# Tag201_GangProgrammerColumnRev1.net
KiCad netlist of a schematic drawn in Altium Designer
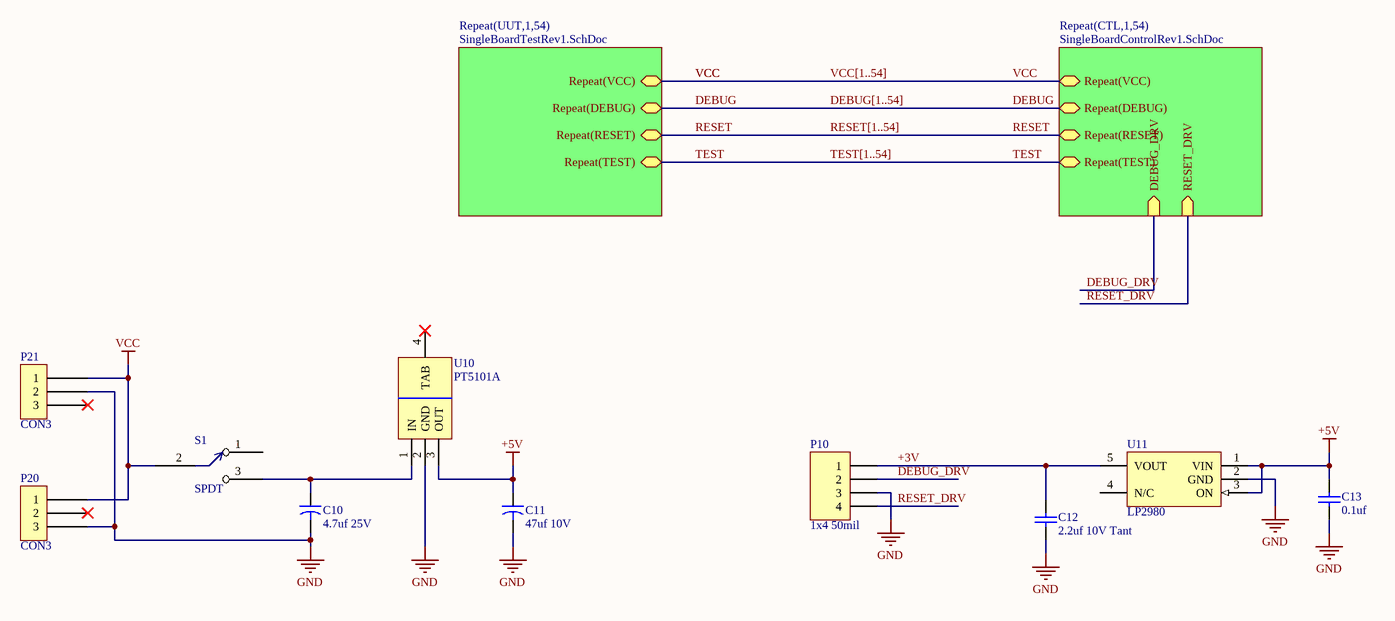
[diagram p0: Tag201_GangProgrammerColumnRev1.SchDoc]

(export (version "E")
  (design (tool "Eeschema 10.0.6"))
  (components
    (comp (ref "C10")
      (value "4.7uf 25V")
      (footprint "CAP C CASE_041412")
      (description "Capacitor")
      (fields (field (name "PARTNO") "T491A475M025AT"))
      (libsource (lib "Miscellaneous Devices") (part "Cap2"))
    )
    (comp (ref "C11")
      (value "47uf 10V")
      (footprint "CAP D CASE_030205")
      (description "Capacitor")
      (fields (field (name "PARTNO") "TAJC476K010RNJ"))
      (libsource (lib "Miscellaneous Devices") (part "Cap2"))
    )
    (comp (ref "C12")
      (value "2.2uf 10V Tant")
      (footprint "CAP A CASE_030205")
      (description "Capacitor")
      (fields (field (name "PARTNO") "F931A225MAA"))
      (libsource (lib "Miscellaneous Devices") (part "Cap"))
    )
    (comp (ref "C13")
      (value "0.1uf")
      (footprint "0603_072205")
      (description "Capacitor")
      (fields (field (name "PARTNO") "C0603C104Z3VACTU"))
      (libsource (lib "Miscellaneous Devices") (part "Cap"))
    )
    (comp (ref "P10")
      (value "1x4 50mil")
      (footprint "1X4 HEADER_50mil_071411")
      (description "Header, 4-Pin")
      (libsource (lib "Miscellaneous Connectors") (part "Header 4"))
    )
    (comp (ref "P20")
      (value "CON3")
      (footprint "POWER JACK_SMALLHOLE_022110")
      (fields (field (name "PARTNO") "PJ-102A"))
      (libsource (lib "Common") (part "CON3"))
    )
    (comp (ref "P21")
      (value "CON3")
      (footprint "Power Jack_SMT_071312")
      (fields (field (name "PARTNO") "PJ-002A-SMT"))
      (libsource (lib "Common") (part "CON3"))
    )
    (comp (ref "S1")
      (value "SPDT")
      (footprint "CnK_TseriesSPDT_Toggle_040512")
      (fields (field (name "PARTNO") "T102SHCQE"))
      (libsource (lib "Common") (part "SWITCH SPST"))
    )
    (comp (ref "U10")
      (value "PT5101A")
      (footprint "TI_PowerTrendsPT_061812")
      (libsource (lib "Common") (part "LM340T"))
    )
    (comp (ref "U11")
      (value "LP2980")
      (footprint "SOT25_030205")
      (fields (field (name "PARTNO") "LP2980AIM5-3.3/NOPB"))
      (libsource (lib "Common") (part "LP2985"))
    )
  )
  (nets
    (net (code "217") (name "+5V") (class "Default")
      (node (ref "C11") (pin "1") (pinfunction "1_1") (pintype "passive"))
      (node (ref "C13") (pin "1") (pinfunction "1_1") (pintype "passive"))
      (node (ref "U10") (pin "3") (pinfunction "OUT_3") (pintype "passive"))
      (node (ref "U11") (pin "1") (pinfunction "VIN_1") (pintype "power_in"))
      (node (ref "U11") (pin "3") (pinfunction "ON_3") (pintype "input"))
    )
    (net (code "218") (name "/+3V") (class "Default")
      (node (ref "C12") (pin "1") (pinfunction "1_1") (pintype "passive"))
      (node (ref "P10") (pin "1") (pinfunction "1_1") (pintype "passive"))
      (node (ref "U11") (pin "5") (pinfunction "VOUT_5") (pintype "power_in"))
    )
    (net (code "221") (name "/DEBUG_DRV") (class "Default")
      (node (ref "P10") (pin "2") (pinfunction "2_2") (pintype "passive"))
    )
    (net (code "224") (name "/RESET_DRV") (class "Default")
      (node (ref "P10") (pin "4") (pinfunction "4_4") (pintype "passive"))
    )
    (net (code "228") (name "GND") (class "Default")
      (node (ref "C10") (pin "2") (pinfunction "2_2") (pintype "passive"))
      (node (ref "C11") (pin "2") (pinfunction "2_2") (pintype "passive"))
      (node (ref "C12") (pin "2") (pinfunction "2_2") (pintype "passive"))
      (node (ref "C13") (pin "2") (pinfunction "2_2") (pintype "passive"))
      (node (ref "P10") (pin "3") (pinfunction "3_3") (pintype "passive"))
      (node (ref "P20") (pin "3") (pinfunction "3_3") (pintype "passive"))
      (node (ref "P21") (pin "2") (pinfunction "2_2") (pintype "passive"))
      (node (ref "U10") (pin "2") (pinfunction "GND_2") (pintype "passive"))
      (node (ref "U11") (pin "2") (pinfunction "GND_2") (pintype "power_in"))
    )
    (net (code "229") (name "Net-(U10-IN)") (class "Default")
      (node (ref "C10") (pin "1") (pinfunction "1_1") (pintype "passive"))
      (node (ref "S1") (pin "3") (pinfunction "3_3") (pintype "passive"))
      (node (ref "U10") (pin "1") (pinfunction "IN_1") (pintype "power_in"))
    )
    (net (code "230") (name "VCC") (class "Default")
      (node (ref "P20") (pin "1") (pinfunction "1_1") (pintype "passive"))
      (node (ref "P21") (pin "1") (pinfunction "1_1") (pintype "passive"))
      (node (ref "S1") (pin "2") (pinfunction "2_2") (pintype "passive"))
    )
    (net (code "231") (name "unconnected-(P20-Pad2)") (class "Default")
      (node (ref "P20") (pin "2") (pinfunction "2_2") (pintype "passive+no_connect"))
    )
    (net (code "232") (name "unconnected-(P21-Pad3)") (class "Default")
      (node (ref "P21") (pin "3") (pinfunction "3_3") (pintype "passive+no_connect"))
    )
    (net (code "233") (name "unconnected-(S1-Pad1)") (class "Default")
      (node (ref "S1") (pin "1") (pinfunction "1_1") (pintype "passive"))
    )
    (net (code "234") (name "unconnected-(U10-TAB-Pad4)") (class "Default")
      (node (ref "U10") (pin "4") (pinfunction "TAB_4") (pintype "passive+no_connect"))
    )
    (net (code "235") (name "unconnected-(U11-N{slash}C-Pad4)") (class "Default")
      (node (ref "U11") (pin "4") (pinfunction "N/C_4") (pintype "passive"))
    )
  )
)
